# schematic.net
KiCad netlist of a schematic drawn in EAGLE
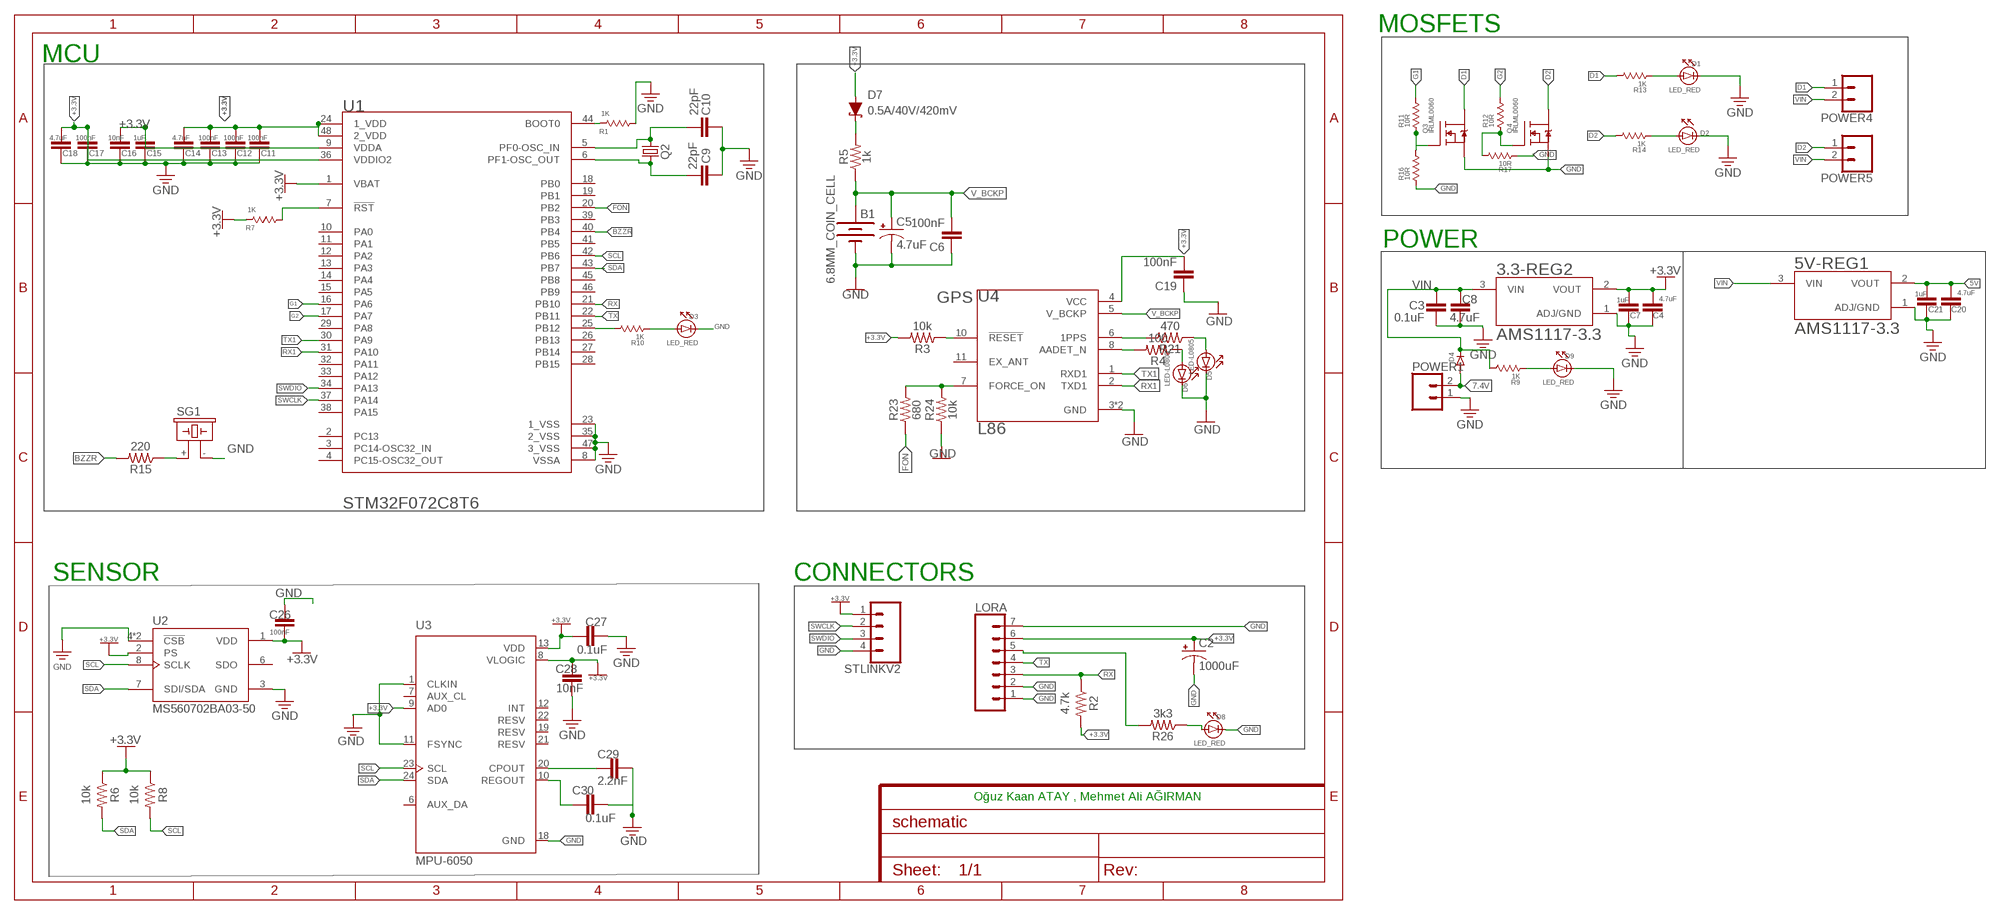
[diagram p0: schematic, sheet 1]

(export (version "E")
  (design (tool "Eeschema 10.0.6"))
  (components
    (comp (ref "3.3-REG2")
      (value "AMS1117-3.3")
      (footprint "eagle-import:SOT229P700X180-4N")
      (fields (field (name "MF") "AMD"))
      (libsource (lib "eagle-import") (part "AMS1117-3.3"))
    )
    (comp (ref "5V-REG1")
      (value "AMS1117-3.3")
      (footprint "eagle-import:SOT229P700X180-4N")
      (fields (field (name "MF") "AMD"))
      (libsource (lib "eagle-import") (part "AMS1117-3.3"))
    )
    (comp (ref "B1")
      (value "6.8MM_COIN_CELL")
      (footprint "eagle-import:BATTCON-6.8MM")
      (libsource (lib "eagle-import") (part "BATTERY-6.8MM_SMD"))
    )
    (comp (ref "C2")
      (value "1000uF")
      (footprint "eagle-import:150CLZ-1010")
      (libsource (lib "eagle-import") (part "CPOL-US150CLZ-1010"))
    )
    (comp (ref "C3")
      (value "0.1uF")
      (footprint "eagle-import:CAPC1608X85")
      (libsource (lib "eagle-import") (part "CCHIP-0603(1608-METRIC)_"))
    )
    (comp (ref "C4")
      (value "4.7uF")
      (footprint "eagle-import:CAPC1608X85")
      (libsource (lib "eagle-import") (part "CCHIP-0603(1608-METRIC)_"))
    )
    (comp (ref "C5")
      (value "4.7uF")
      (footprint "eagle-import:EIA3216")
      (libsource (lib "eagle-import") (part "10UF-POLAR-EIA3216-16V-10%(TANT)"))
    )
    (comp (ref "C6")
      (value "100nF")
      (footprint "eagle-import:0603")
      (libsource (lib "eagle-import") (part "1.0UF-0603-16V-10%"))
    )
    (comp (ref "C7")
      (value "1uF")
      (footprint "eagle-import:CAPC1608X85")
      (libsource (lib "eagle-import") (part "CCHIP-0603(1608-METRIC)_"))
    )
    (comp (ref "C8")
      (value "4.7uF")
      (footprint "eagle-import:CAPC1608X85")
      (libsource (lib "eagle-import") (part "CCHIP-0603(1608-METRIC)_"))
    )
    (comp (ref "C9")
      (value "22pF")
      (footprint "eagle-import:CAPC1608X85")
      (libsource (lib "eagle-import") (part "CCHIP-0603(1608-METRIC)_"))
    )
    (comp (ref "C10")
      (value "22pF")
      (footprint "eagle-import:CAPC1608X85")
      (libsource (lib "eagle-import") (part "CCHIP-0603(1608-METRIC)_"))
    )
    (comp (ref "C11")
      (value "100nF")
      (footprint "eagle-import:CAPC1608X85")
      (libsource (lib "eagle-import") (part "CCHIP-0603(1608-METRIC)_"))
    )
    (comp (ref "C12")
      (value "100nF")
      (footprint "eagle-import:CAPC1608X85")
      (libsource (lib "eagle-import") (part "CCHIP-0603(1608-METRIC)_"))
    )
    (comp (ref "C13")
      (value "100nF")
      (footprint "eagle-import:CAPC1608X85")
      (libsource (lib "eagle-import") (part "CCHIP-0603(1608-METRIC)_"))
    )
    (comp (ref "C14")
      (value "4.7uF")
      (footprint "eagle-import:CAPC1608X85")
      (libsource (lib "eagle-import") (part "CCHIP-0603(1608-METRIC)_"))
    )
    (comp (ref "C15")
      (value "1uF")
      (footprint "eagle-import:CAPC1608X85")
      (libsource (lib "eagle-import") (part "CCHIP-0603(1608-METRIC)_"))
    )
    (comp (ref "C16")
      (value "10nF")
      (footprint "eagle-import:CAPC1608X85")
      (libsource (lib "eagle-import") (part "CCHIP-0603(1608-METRIC)_"))
    )
    (comp (ref "C17")
      (value "100nF")
      (footprint "eagle-import:CAPC1608X85")
      (libsource (lib "eagle-import") (part "CCHIP-0603(1608-METRIC)_"))
    )
    (comp (ref "C18")
      (value "4.7uF")
      (footprint "eagle-import:CAPC1608X85")
      (libsource (lib "eagle-import") (part "CCHIP-0603(1608-METRIC)_"))
    )
    (comp (ref "C19")
      (value "100nF")
      (footprint "eagle-import:0603")
      (libsource (lib "eagle-import") (part "1.0UF-0603-16V-10%"))
    )
    (comp (ref "C20")
      (value "4.7uF")
      (footprint "eagle-import:CAPC1608X85")
      (libsource (lib "eagle-import") (part "CCHIP-0603(1608-METRIC)_"))
    )
    (comp (ref "C21")
      (value "1uF")
      (footprint "eagle-import:CAPC1608X85")
      (libsource (lib "eagle-import") (part "CCHIP-0603(1608-METRIC)_"))
    )
    (comp (ref "C26")
      (value "100nF")
      (footprint "eagle-import:CAPC1608X85")
      (libsource (lib "eagle-import") (part "CCHIP-0603(1608-METRIC)_"))
    )
    (comp (ref "C27")
      (value "0.1uF")
      (footprint "eagle-import:CAPC1608X85")
      (libsource (lib "eagle-import") (part "CCHIP-0603(1608-METRIC)_"))
    )
    (comp (ref "C28")
      (value "10nF")
      (footprint "eagle-import:CAPC1608X85")
      (libsource (lib "eagle-import") (part "CCHIP-0603(1608-METRIC)_"))
    )
    (comp (ref "C29")
      (value "2.2nF")
      (footprint "eagle-import:CAPC1608X85")
      (libsource (lib "eagle-import") (part "CCHIP-0603(1608-METRIC)_"))
    )
    (comp (ref "C30")
      (value "0.1uF")
      (footprint "eagle-import:CAPC1608X85")
      (libsource (lib "eagle-import") (part "CCHIP-0603(1608-METRIC)_"))
    )
    (comp (ref "D1")
      (value "LED_RED")
      (footprint "eagle-import:LED_0805")
      (libsource (lib "eagle-import") (part "LED-L0805"))
    )
    (comp (ref "D2")
      (value "LED_RED")
      (footprint "eagle-import:LED_0805")
      (libsource (lib "eagle-import") (part "LED-L0805"))
    )
    (comp (ref "D3")
      (value "LED_RED")
      (footprint "eagle-import:LED_0805")
      (libsource (lib "eagle-import") (part "LED-L0805"))
    )
    (comp (ref "D4")
      (value "DIODE-SS14-DO214AC")
      (footprint "eagle-import:DO-214AC")
      (libsource (lib "eagle-import") (part "DIODE-SS14-DO214AC"))
    )
    (comp (ref "D5")
      (value "LED-L0805")
      (footprint "eagle-import:LED_0805")
      (libsource (lib "eagle-import") (part "LED-L0805"))
    )
    (comp (ref "D6")
      (value "LED-L0805")
      (footprint "eagle-import:LED_0805")
      (libsource (lib "eagle-import") (part "LED-L0805"))
    )
    (comp (ref "D7")
      (value "0.5A/40V/420mV")
      (footprint "eagle-import:SOD-323")
      (libsource (lib "eagle-import") (part "DIODE-SCHOTTKY-PMEG4005EJ"))
    )
    (comp (ref "D8")
      (value "LED_RED")
      (footprint "eagle-import:LED_0805")
      (libsource (lib "eagle-import") (part "LED-L0805"))
    )
    (comp (ref "D9")
      (value "LED_RED")
      (footprint "eagle-import:LED_0805")
      (libsource (lib "eagle-import") (part "LED-L0805"))
    )
    (comp (ref "LORA")
      (value "CONN_07")
      (footprint "eagle-import:1X07")
      (libsource (lib "eagle-import") (part "CONN_07"))
    )
    (comp (ref "POWER1")
      (value "CONN_023.5MM-NO_SILK")
      (footprint "eagle-import:SCREWTERMINAL-3.5MM-2-NS")
      (libsource (lib "eagle-import") (part "CONN_023.5MM-NO_SILK"))
    )
    (comp (ref "POWER4")
      (value "CONN_023.5MM-NO_SILK")
      (footprint "eagle-import:SCREWTERMINAL-3.5MM-2-NS")
      (libsource (lib "eagle-import") (part "CONN_023.5MM-NO_SILK"))
    )
    (comp (ref "POWER5")
      (value "CONN_023.5MM-NO_SILK")
      (footprint "eagle-import:SCREWTERMINAL-3.5MM-2-NS")
      (libsource (lib "eagle-import") (part "CONN_023.5MM-NO_SILK"))
    )
    (comp (ref "Q2")
      (value "CRYSTALHC49U70")
      (footprint "eagle-import:HC49U70")
      (libsource (lib "eagle-import") (part "CRYSTALHC49U70"))
    )
    (comp (ref "Q3")
      (value "IRLML0060")
      (footprint "eagle-import:SOT-23")
      (libsource (lib "eagle-import") (part "N_CH_MOSFET-SOT23"))
    )
    (comp (ref "Q4")
      (value "IRLML0060")
      (footprint "eagle-import:SOT-23")
      (libsource (lib "eagle-import") (part "N_CH_MOSFET-SOT23"))
    )
    (comp (ref "R1")
      (value "1K")
      (footprint "eagle-import:RES_0805")
      (libsource (lib "eagle-import") (part "RES-R0805"))
    )
    (comp (ref "R2")
      (value "4.7k")
      (footprint "eagle-import:RESC2012X65")
      (libsource (lib "eagle-import") (part "R-USCHIP-0805(2012-METRIC)_"))
    )
    (comp (ref "R3")
      (value "10k")
      (footprint "eagle-import:0603")
      (libsource (lib "eagle-import") (part "SparkFun-Resistors_532_1KOHM-0603-1/10W-1%"))
    )
    (comp (ref "R4")
      (value "100")
      (footprint "eagle-import:0603")
      (libsource (lib "eagle-import") (part "SparkFun-Resistors_532_1KOHM-0603-1/10W-1%"))
    )
    (comp (ref "R5")
      (value "1k")
      (footprint "eagle-import:0603")
      (libsource (lib "eagle-import") (part "1KOHM-0603-1/10W-1%"))
    )
    (comp (ref "R6")
      (value "10k")
      (footprint "eagle-import:RESC2012X65")
      (libsource (lib "eagle-import") (part "R-USCHIP-0805(2012-METRIC)_"))
    )
    (comp (ref "R7")
      (value "1K")
      (footprint "eagle-import:RES_0805")
      (libsource (lib "eagle-import") (part "RES-R0805"))
    )
    (comp (ref "R8")
      (value "10k")
      (footprint "eagle-import:RESC2012X65")
      (libsource (lib "eagle-import") (part "R-USCHIP-0805(2012-METRIC)_"))
    )
    (comp (ref "R9")
      (value "1K")
      (footprint "eagle-import:RES_0805")
      (libsource (lib "eagle-import") (part "RES-R0805"))
    )
    (comp (ref "R10")
      (value "1K")
      (footprint "eagle-import:RES_0805")
      (libsource (lib "eagle-import") (part "RES-R0805"))
    )
    (comp (ref "R11")
      (value "10R")
      (footprint "eagle-import:RES_0805")
      (libsource (lib "eagle-import") (part "RES-R0805"))
    )
    (comp (ref "R12")
      (value "10R")
      (footprint "eagle-import:RES_0805")
      (libsource (lib "eagle-import") (part "RES-R0805"))
    )
    (comp (ref "R13")
      (value "1K")
      (footprint "eagle-import:RES_0805")
      (libsource (lib "eagle-import") (part "RES-R0805"))
    )
    (comp (ref "R14")
      (value "1K")
      (footprint "eagle-import:RES_0805")
      (libsource (lib "eagle-import") (part "RES-R0805"))
    )
    (comp (ref "R15")
      (value "220")
      (footprint "eagle-import:0603")
      (libsource (lib "eagle-import") (part "SparkFun-Resistors_532_1KOHM-0603-1/10W-1%"))
    )
    (comp (ref "R16")
      (value "10R")
      (footprint "eagle-import:RES_0805")
      (libsource (lib "eagle-import") (part "RES-R0805"))
    )
    (comp (ref "R17")
      (value "10R")
      (footprint "eagle-import:RES_0805")
      (libsource (lib "eagle-import") (part "RES-R0805"))
    )
    (comp (ref "R21")
      (value "470")
      (footprint "eagle-import:0603")
      (libsource (lib "eagle-import") (part "SparkFun-Resistors_532_1KOHM-0603-1/10W-1%"))
    )
    (comp (ref "R23")
      (value "680")
      (footprint "eagle-import:0603")
      (libsource (lib "eagle-import") (part "SparkFun-Resistors_532_1KOHM-0603-1/10W-1%"))
    )
    (comp (ref "R24")
      (value "10k")
      (footprint "eagle-import:0603")
      (libsource (lib "eagle-import") (part "SparkFun-Resistors_532_1KOHM-0603-1/10W-1%"))
    )
    (comp (ref "R26")
      (value "3k3")
      (footprint "eagle-import:0603")
      (libsource (lib "eagle-import") (part "SparkFun-Resistors_532_1KOHM-0603-1/10W-1%"))
    )
    (comp (ref "SG1")
      (value "F/CM12P")
      (footprint "eagle-import:F_CM12P")
      (libsource (lib "eagle-import") (part "F/CM12P"))
    )
    (comp (ref "STLINKV2")
      (value "CONN_04")
      (footprint "eagle-import:1X04")
      (libsource (lib "eagle-import") (part "CONN_04"))
    )
    (comp (ref "U1")
      (value "STMICROELECTRONICS_STM32F072C8T6STMICROELECTRONICS_STM32F072C8T6_0_0")
      (footprint "eagle-import:STMICROELECTRONICS_STM32F072C8T6_0")
      (fields
        (field (name "DIGIKEY_PART_NUMBER") "STM32F072C8T6-ND")
        (field (name "MF") "STMicroelectronics")
        (field (name "MOUSER_PART_NUMBER") "511-STM32F072C8T6")
      )
      (libsource (lib "eagle-import") (part "STMICROELECTRONICS_STM32F072C8T6STMICROELECTRONICS_STM32F072C8T6_0_0"))
    )
    (comp (ref "U2")
      (value "MS560702BA03-50")
      (footprint "eagle-import:SON125P300X500X100-8N")
      (fields (field (name "MF") "TE Connectivity"))
      (libsource (lib "eagle-import") (part "MS560702BA03-50"))
    )
    (comp (ref "U3")
      (value "MPU-6050")
      (footprint "eagle-import:QFN50P400X400X95-24N")
      (fields (field (name "MF") "TDK InvenSense"))
      (libsource (lib "eagle-import") (part "MPU-6050"))
    )
    (comp (ref "U4")
      (value "L86")
      (footprint "eagle-import:XCVR_L86")
      (fields (field (name "MF") "Quectel"))
      (libsource (lib "eagle-import") (part "L86"))
    )
  )
  (nets
    (net (code "1") (name "+3.3V") (class "Default")
      (node (ref "3.3-REG2") (pin "2") (pinfunction "VOUT_2") (pintype "output"))
      (node (ref "C11") (pin "1") (pinfunction "1_1") (pintype "passive"))
      (node (ref "C12") (pin "1") (pinfunction "1_1") (pintype "passive"))
      (node (ref "C13") (pin "1") (pinfunction "1_1") (pintype "passive"))
      (node (ref "C14") (pin "1") (pinfunction "1_1") (pintype "passive"))
      (node (ref "C15") (pin "1") (pinfunction "1_1") (pintype "passive"))
      (node (ref "C16") (pin "1") (pinfunction "1_1") (pintype "passive"))
      (node (ref "C17") (pin "1") (pinfunction "1_1") (pintype "passive"))
      (node (ref "C18") (pin "1") (pinfunction "1_1") (pintype "passive"))
      (node (ref "C19") (pin "2") (pinfunction "2_2") (pintype "passive"))
      (node (ref "C2") (pin "+") (pinfunction "+_+") (pintype "passive"))
      (node (ref "C26") (pin "1") (pinfunction "1_1") (pintype "passive"))
      (node (ref "C27") (pin "2") (pinfunction "2_2") (pintype "passive"))
      (node (ref "C28") (pin "2") (pinfunction "2_2") (pintype "passive"))
      (node (ref "C4") (pin "1") (pinfunction "1_1") (pintype "passive"))
      (node (ref "C7") (pin "1") (pinfunction "1_1") (pintype "passive"))
      (node (ref "D7") (pin "A") (pinfunction "A_A") (pintype "passive"))
      (node (ref "LORA") (pin "6") (pinfunction "6_6") (pintype "passive"))
      (node (ref "R2") (pin "2") (pinfunction "2_2") (pintype "passive"))
      (node (ref "R3") (pin "2") (pinfunction "2_2") (pintype "passive"))
      (node (ref "R6") (pin "1") (pinfunction "1_1") (pintype "passive"))
      (node (ref "R7") (pin "B") (pinfunction "B_B") (pintype "bidirectional"))
      (node (ref "R8") (pin "1") (pinfunction "1_1") (pintype "passive"))
      (node (ref "STLINKV2") (pin "1") (pinfunction "1_1") (pintype "passive"))
      (node (ref "U1") (pin "1") (pinfunction "VBAT_1") (pintype "bidirectional"))
      (node (ref "U1") (pin "24") (pinfunction "1_VDD_24") (pintype "bidirectional"))
      (node (ref "U1") (pin "36") (pinfunction "VDDIO2_36") (pintype "bidirectional"))
      (node (ref "U1") (pin "48") (pinfunction "2_VDD_48") (pintype "bidirectional"))
      (node (ref "U1") (pin "9") (pinfunction "VDDA_9") (pintype "bidirectional"))
      (node (ref "U2") (pin "1") (pinfunction "VDD_1") (pintype "power_in"))
      (node (ref "U2") (pin "2") (pinfunction "PS_2") (pintype "input"))
      (node (ref "U3") (pin "13") (pinfunction "VDD_13") (pintype "power_in"))
      (node (ref "U3") (pin "8") (pinfunction "VLOGIC_8") (pintype "power_in"))
      (node (ref "U3") (pin "9") (pinfunction "AD0_9") (pintype "input"))
      (node (ref "U4") (pin "4") (pinfunction "VCC_4") (pintype "power_in"))
    )
    (net (code "2") (name "5V") (class "Default")
      (node (ref "5V-REG1") (pin "2") (pinfunction "VOUT_2") (pintype "output"))
      (node (ref "C20") (pin "1") (pinfunction "1_1") (pintype "passive"))
      (node (ref "C21") (pin "1") (pinfunction "1_1") (pintype "passive"))
    )
    (net (code "3") (name "7.4V") (class "Default")
      (node (ref "D4") (pin "A") (pinfunction "ANOT_A") (pintype "bidirectional"))
      (node (ref "POWER1") (pin "2") (pinfunction "2_2") (pintype "passive"))
    )
    (net (code "4") (name "BZZR") (class "Default")
      (node (ref "R15") (pin "2") (pinfunction "2_2") (pintype "passive"))
      (node (ref "U1") (pin "40") (pinfunction "PB4_40") (pintype "bidirectional"))
    )
    (net (code "5") (name "D1") (class "Default")
      (node (ref "POWER4") (pin "1") (pinfunction "1_1") (pintype "passive"))
      (node (ref "Q3") (pin "3") (pinfunction "D_3") (pintype "bidirectional"))
      (node (ref "R13") (pin "B") (pinfunction "B_B") (pintype "bidirectional"))
    )
    (net (code "6") (name "D2") (class "Default")
      (node (ref "POWER5") (pin "1") (pinfunction "1_1") (pintype "passive"))
      (node (ref "Q4") (pin "3") (pinfunction "D_3") (pintype "bidirectional"))
      (node (ref "R14") (pin "B") (pinfunction "B_B") (pintype "bidirectional"))
    )
    (net (code "7") (name "FON") (class "Default")
      (node (ref "R23") (pin "1") (pinfunction "1_1") (pintype "passive"))
      (node (ref "U1") (pin "20") (pinfunction "PB2_20") (pintype "bidirectional"))
    )
    (net (code "8") (name "G1") (class "Default")
      (node (ref "R11") (pin "B") (pinfunction "B_B") (pintype "bidirectional"))
      (node (ref "U1") (pin "16") (pinfunction "PA6_16") (pintype "bidirectional"))
    )
    (net (code "9") (name "G2") (class "Default")
      (node (ref "R12") (pin "B") (pinfunction "B_B") (pintype "bidirectional"))
      (node (ref "U1") (pin "17") (pinfunction "PA7_17") (pintype "bidirectional"))
    )
    (net (code "10") (name "GND") (class "Default")
      (node (ref "3.3-REG2") (pin "1") (pinfunction "ADJ/GND_1") (pintype "power_in"))
      (node (ref "5V-REG1") (pin "1") (pinfunction "ADJ/GND_1") (pintype "power_in"))
      (node (ref "B1") (pin "-") (pinfunction "-_-") (pintype "power_in"))
      (node (ref "C10") (pin "2") (pinfunction "2_2") (pintype "passive"))
      (node (ref "C11") (pin "2") (pinfunction "2_2") (pintype "passive"))
      (node (ref "C12") (pin "2") (pinfunction "2_2") (pintype "passive"))
      (node (ref "C13") (pin "2") (pinfunction "2_2") (pintype "passive"))
      (node (ref "C14") (pin "2") (pinfunction "2_2") (pintype "passive"))
      (node (ref "C15") (pin "2") (pinfunction "2_2") (pintype "passive"))
      (node (ref "C16") (pin "2") (pinfunction "2_2") (pintype "passive"))
      (node (ref "C17") (pin "2") (pinfunction "2_2") (pintype "passive"))
      (node (ref "C18") (pin "2") (pinfunction "2_2") (pintype "passive"))
      (node (ref "C19") (pin "1") (pinfunction "1_1") (pintype "passive"))
      (node (ref "C2") (pin "-") (pinfunction "-_-") (pintype "passive"))
      (node (ref "C20") (pin "2") (pinfunction "2_2") (pintype "passive"))
      (node (ref "C21") (pin "2") (pinfunction "2_2") (pintype "passive"))
      (node (ref "C26") (pin "2") (pinfunction "2_2") (pintype "passive"))
      (node (ref "C27") (pin "1") (pinfunction "1_1") (pintype "passive"))
      (node (ref "C28") (pin "1") (pinfunction "1_1") (pintype "passive"))
      (node (ref "C29") (pin "1") (pinfunction "1_1") (pintype "passive"))
      (node (ref "C3") (pin "1") (pinfunction "1_1") (pintype "passive"))
      (node (ref "C30") (pin "1") (pinfunction "1_1") (pintype "passive"))
      (node (ref "C4") (pin "2") (pinfunction "2_2") (pintype "passive"))
      (node (ref "C5") (pin "-") (pinfunction "-_-") (pintype "passive"))
      (node (ref "C6") (pin "1") (pinfunction "1_1") (pintype "passive"))
      (node (ref "C7") (pin "2") (pinfunction "2_2") (pintype "passive"))
      (node (ref "C8") (pin "1") (pinfunction "1_1") (pintype "passive"))
      (node (ref "C9") (pin "2") (pinfunction "2_2") (pintype "passive"))
      (node (ref "D1") (pin "K") (pinfunction "KATOT_K") (pintype "bidirectional"))
      (node (ref "D2") (pin "K") (pinfunction "KATOT_K") (pintype "bidirectional"))
      (node (ref "D3") (pin "K") (pinfunction "KATOT_K") (pintype "bidirectional"))
      (node (ref "D5") (pin "K") (pinfunction "KATOT_K") (pintype "bidirectional"))
      (node (ref "D6") (pin "K") (pinfunction "KATOT_K") (pintype "bidirectional"))
      (node (ref "D8") (pin "K") (pinfunction "KATOT_K") (pintype "bidirectional"))
      (node (ref "D9") (pin "K") (pinfunction "KATOT_K") (pintype "bidirectional"))
      (node (ref "LORA") (pin "1") (pinfunction "1_1") (pintype "passive"))
      (node (ref "LORA") (pin "2") (pinfunction "2_2") (pintype "passive"))
      (node (ref "LORA") (pin "7") (pinfunction "7_7") (pintype "passive"))
      (node (ref "POWER1") (pin "1") (pinfunction "1_1") (pintype "passive"))
      (node (ref "Q3") (pin "2") (pinfunction "S_2") (pintype "bidirectional"))
      (node (ref "Q4") (pin "2") (pinfunction "S_2") (pintype "bidirectional"))
      (node (ref "R1") (pin "A") (pinfunction "A_A") (pintype "bidirectional"))
      (node (ref "R16") (pin "A") (pinfunction "A_A") (pintype "bidirectional"))
      (node (ref "R17") (pin "A") (pinfunction "A_A") (pintype "bidirectional"))
      (node (ref "R24") (pin "1") (pinfunction "1_1") (pintype "passive"))
      (node (ref "SG1") (pin "-") (pinfunction "2_-") (pintype "passive"))
      (node (ref "STLINKV2") (pin "4") (pinfunction "4_4") (pintype "passive"))
      (node (ref "U1") (pin "23") (pinfunction "1_VSS_23") (pintype "bidirectional"))
      (node (ref "U1") (pin "35") (pinfunction "2_VSS_35") (pintype "bidirectional"))
      (node (ref "U1") (pin "47") (pinfunction "3_VSS_47") (pintype "bidirectional"))
      (node (ref "U1") (pin "8") (pinfunction "VSSA_8") (pintype "bidirectional"))
      (node (ref "U2") (pin "3") (pinfunction "GND_3") (pintype "power_in"))
      (node (ref "U2") (pin "4") (pinfunction "~{CSB}_4") (pintype "input"))
      (node (ref "U2") (pin "5") (pinfunction "~{CSB}_5") (pintype "input"))
      (node (ref "U3") (pin "1") (pinfunction "CLKIN_1") (pintype "input"))
      (node (ref "U3") (pin "11") (pinfunction "FSYNC_11") (pintype "input"))
      (node (ref "U3") (pin "18") (pinfunction "GND_18") (pintype "power_in"))
      (node (ref "U4") (pin "12") (pinfunction "GND_12") (pintype "passive"))
      (node (ref "U4") (pin "3") (pinfunction "GND_3") (pintype "passive"))
    )
    (net (code "11") (name "Net-(D1-ANOT)") (class "Default")
      (node (ref "D1") (pin "A") (pinfunction "ANOT_A") (pintype "bidirectional"))
      (node (ref "R13") (pin "A") (pinfunction "A_A") (pintype "bidirectional"))
    )
    (net (code "12") (name "Net-(D2-ANOT)") (class "Default")
      (node (ref "D2") (pin "A") (pinfunction "ANOT_A") (pintype "bidirectional"))
      (node (ref "R14") (pin "A") (pinfunction "A_A") (pintype "bidirectional"))
    )
    (net (code "13") (name "Net-(D3-ANOT)") (class "Default")
      (node (ref "D3") (pin "A") (pinfunction "ANOT_A") (pintype "bidirectional"))
      (node (ref "R10") (pin "A") (pinfunction "A_A") (pintype "bidirectional"))
    )
    (net (code "14") (name "Net-(D5-ANOT)") (class "Default")
      (node (ref "D5") (pin "A") (pinfunction "ANOT_A") (pintype "bidirectional"))
      (node (ref "R21") (pin "1") (pinfunction "1_1") (pintype "passive"))
    )
    (net (code "15") (name "Net-(D6-ANOT)") (class "Default")
      (node (ref "D6") (pin "A") (pinfunction "ANOT_A") (pintype "bidirectional"))
      (node (ref "R4") (pin "1") (pinfunction "1_1") (pintype "passive"))
    )
    (net (code "16") (name "Net-(D7-PadC)") (class "Default")
      (node (ref "D7") (pin "C") (pinfunction "C_C") (pintype "passive"))
      (node (ref "R5") (pin "2") (pinfunction "2_2") (pintype "passive"))
    )
    (net (code "17") (name "Net-(D8-ANOT)") (class "Default")
      (node (ref "D8") (pin "A") (pinfunction "ANOT_A") (pintype "bidirectional"))
      (node (ref "R26") (pin "1") (pinfunction "1_1") (pintype "passive"))
    )
    (net (code "18") (name "Net-(D9-ANOT)") (class "Default")
      (node (ref "D9") (pin "A") (pinfunction "ANOT_A") (pintype "bidirectional"))
      (node (ref "R9") (pin "A") (pinfunction "A_A") (pintype "bidirectional"))
    )
    (net (code "19") (name "Net-(LORA-Pad5)") (class "Default")
      (node (ref "LORA") (pin "5") (pinfunction "5_5") (pintype "passive"))
      (node (ref "R26") (pin "2") (pinfunction "2_2") (pintype "passive"))
    )
    (net (code "20") (name "Net-(Q3-G)") (class "Default")
      (node (ref "Q3") (pin "1") (pinfunction "G_1") (pintype "bidirectional"))
      (node (ref "R11") (pin "A") (pinfunction "A_A") (pintype "bidirectional"))
      (node (ref "R16") (pin "B") (pinfunction "B_B") (pintype "bidirectional"))
    )
    (net (code "21") (name "Net-(Q4-G)") (class "Default")
      (node (ref "Q4") (pin "1") (pinfunction "G_1") (pintype "bidirectional"))
      (node (ref "R12") (pin "A") (pinfunction "A_A") (pintype "bidirectional"))
      (node (ref "R17") (pin "B") (pinfunction "B_B") (pintype "bidirectional"))
    )
    (net (code "22") (name "Net-(SG1-1)") (class "Default")
      (node (ref "R15") (pin "1") (pinfunction "1_1") (pintype "passive"))
      (node (ref "SG1") (pin "+") (pinfunction "1_+") (pintype "passive"))
    )
    (net (code "23") (name "Net-(U1-BOOT0)") (class "Default")
      (node (ref "R1") (pin "B") (pinfunction "B_B") (pintype "bidirectional"))
      (node (ref "U1") (pin "44") (pinfunction "BOOT0_44") (pintype "bidirectional"))
    )
    (net (code "24") (name "Net-(U1-PB12)") (class "Default")
      (node (ref "R10") (pin "B") (pinfunction "B_B") (pintype "bidirectional"))
      (node (ref "U1") (pin "25") (pinfunction "PB12_25") (pintype "bidirectional"))
    )
    (net (code "25") (name "Net-(U1-PF0-OSC_IN)") (class "Default")
      (node (ref "C10") (pin "1") (pinfunction "1_1") (pintype "passive"))
      (node (ref "Q2") (pin "1") (pinfunction "1_1") (pintype "passive"))
      (node (ref "U1") (pin "5") (pinfunction "PF0-OSC_IN_5") (pintype "bidirectional"))
    )
    (net (code "26") (name "Net-(U1-PF1-OSC_OUT)") (class "Default")
      (node (ref "C9") (pin "1") (pinfunction "1_1") (pintype "passive"))
      (node (ref "Q2") (pin "2") (pinfunction "2_2") (pintype "passive"))
      (node (ref "U1") (pin "6") (pinfunction "PF1-OSC_OUT_6") (pintype "bidirectional"))
    )
    (net (code "27") (name "Net-(U1-~{RST})") (class "Default")
      (node (ref "R7") (pin "A") (pinfunction "A_A") (pintype "bidirectional"))
      (node (ref "U1") (pin "7") (pinfunction "~{RST}_7") (pintype "bidirectional"))
    )
    (net (code "28") (name "Net-(U3-CPOUT)") (class "Default")
      (node (ref "C29") (pin "2") (pinfunction "2_2") (pintype "passive"))
      (node (ref "U3") (pin "20") (pinfunction "CPOUT_20") (pintype "passive"))
    )
    (net (code "29") (name "Net-(U3-REGOUT)") (class "Default")
      (node (ref "C30") (pin "2") (pinfunction "2_2") (pintype "passive"))
      (node (ref "U3") (pin "10") (pinfunction "REGOUT_10") (pintype "passive"))
    )
    (net (code "30") (name "Net-(U4-1PPS)") (class "Default")
      (node (ref "R21") (pin "2") (pinfunction "2_2") (pintype "passive"))
      (node (ref "U4") (pin "6") (pinfunction "1PPS_6") (pintype "output"))
    )
    (net (code "31") (name "Net-(U4-AADET_N)") (class "Default")
      (node (ref "R4") (pin "2") (pinfunction "2_2") (pintype "passive"))
      (node (ref "U4") (pin "8") (pinfunction "AADET_N_8") (pintype "output"))
    )
    (net (code "32") (name "Net-(U4-FORCE_ON)") (class "Default")
      (node (ref "R23") (pin "2") (pinfunction "2_2") (pintype "passive"))
      (node (ref "R24") (pin "2") (pinfunction "2_2") (pintype "passive"))
      (node (ref "U4") (pin "7") (pinfunction "FORCE_ON_7") (pintype "input"))
    )
    (net (code "33") (name "Net-(U4-~{RESET})") (class "Default")
      (node (ref "R3") (pin "1") (pinfunction "1_1") (pintype "passive"))
      (node (ref "U4") (pin "10") (pinfunction "~{RESET}_10") (pintype "input"))
    )
    (net (code "34") (name "RX") (class "Default")
      (node (ref "LORA") (pin "3") (pinfunction "3_3") (pintype "passive"))
      (node (ref "R2") (pin "1") (pinfunction "1_1") (pintype "passive"))
      (node (ref "U1") (pin "21") (pinfunction "PB10_21") (pintype "bidirectional"))
    )
    (net (code "35") (name "RX1") (class "Default")
      (node (ref "U1") (pin "31") (pinfunction "PA10_31") (pintype "bidirectional"))
      (node (ref "U4") (pin "2") (pinfunction "TXD1_2") (pintype "output"))
    )
    (net (code "36") (name "SCL") (class "Default")
      (node (ref "R8") (pin "2") (pinfunction "2_2") (pintype "passive"))
      (node (ref "U1") (pin "42") (pinfunction "PB6_42") (pintype "bidirectional"))
      (node (ref "U2") (pin "8") (pinfunction "SCLK_8") (pintype "input"))
      (node (ref "U3") (pin "23") (pinfunction "SCL_23") (pintype "input"))
    )
    (net (code "37") (name "SDA") (class "Default")
      (node (ref "R6") (pin "2") (pinfunction "2_2") (pintype "passive"))
      (node (ref "U1") (pin "43") (pinfunction "PB7_43") (pintype "bidirectional"))
      (node (ref "U2") (pin "7") (pinfunction "SDI/SDA_7") (pintype "bidirectional"))
      (node (ref "U3") (pin "24") (pinfunction "SDA_24") (pintype "bidirectional"))
    )
    (net (code "38") (name "SWCLK") (class "Default")
      (node (ref "STLINKV2") (pin "2") (pinfunction "2_2") (pintype "passive"))
      (node (ref "U1") (pin "37") (pinfunction "PA14_37") (pintype "bidirectional"))
    )
    (net (code "39") (name "SWDIO") (class "Default")
      (node (ref "STLINKV2") (pin "3") (pinfunction "3_3") (pintype "passive"))
      (node (ref "U1") (pin "34") (pinfunction "PA13_34") (pintype "bidirectional"))
    )
    (net (code "40") (name "TX") (class "Default")
      (node (ref "LORA") (pin "4") (pinfunction "4_4") (pintype "passive"))
      (node (ref "U1") (pin "22") (pinfunction "PB11_22") (pintype "bidirectional"))
    )
    (net (code "41") (name "TX1") (class "Default")
      (node (ref "U1") (pin "30") (pinfunction "PA9_30") (pintype "bidirectional"))
      (node (ref "U4") (pin "1") (pinfunction "RXD1_1") (pintype "input"))
    )
    (net (code "42") (name "VIN") (class "Default")
      (node (ref "3.3-REG2") (pin "3") (pinfunction "VIN_3") (pintype "input"))
      (node (ref "5V-REG1") (pin "3") (pinfunction "VIN_3") (pintype "input"))
      (node (ref "C3") (pin "2") (pinfunction "2_2") (pintype "passive"))
      (node (ref "C8") (pin "2") (pinfunction "2_2") (pintype "passive"))
      (node (ref "D4") (pin "K") (pinfunction "KATOT_K") (pintype "bidirectional"))
      (node (ref "POWER4") (pin "2") (pinfunction "2_2") (pintype "passive"))
      (node (ref "POWER5") (pin "2") (pinfunction "2_2") (pintype "passive"))
      (node (ref "R9") (pin "B") (pinfunction "B_B") (pintype "bidirectional"))
    )
    (net (code "43") (name "V_BCKP") (class "Default")
      (node (ref "B1") (pin "+") (pinfunction "+_+") (pintype "power_in"))
      (node (ref "C5") (pin "+") (pinfunction "+_+") (pintype "passive"))
      (node (ref "C6") (pin "2") (pinfunction "2_2") (pintype "passive"))
      (node (ref "R5") (pin "1") (pinfunction "1_1") (pintype "passive"))
      (node (ref "U4") (pin "5") (pinfunction "V_BCKP_5") (pintype "power_in"))
    )
    (net (code "44") (name "unconnected-(U1-PA0-Pad10)") (class "Default")
      (node (ref "U1") (pin "10") (pinfunction "PA0_10") (pintype "bidirectional"))
    )
    (net (code "45") (name "unconnected-(U1-PA1-Pad11)") (class "Default")
      (node (ref "U1") (pin "11") (pinfunction "PA1_11") (pintype "bidirectional"))
    )
    (net (code "46") (name "unconnected-(U1-PA2-Pad12)") (class "Default")
      (node (ref "U1") (pin "12") (pinfunction "PA2_12") (pintype "bidirectional"))
    )
    (net (code "47") (name "unconnected-(U1-PA3-Pad13)") (class "Default")
      (node (ref "U1") (pin "13") (pinfunction "PA3_13") (pintype "bidirectional"))
    )
    (net (code "48") (name "unconnected-(U1-PA4-Pad14)") (class "Default")
      (node (ref "U1") (pin "14") (pinfunction "PA4_14") (pintype "bidirectional"))
    )
    (net (code "49") (name "unconnected-(U1-PA5-Pad15)") (class "Default")
      (node (ref "U1") (pin "15") (pinfunction "PA5_15") (pintype "bidirectional"))
    )
    (net (code "50") (name "unconnected-(U1-PA8-Pad29)") (class "Default")
      (node (ref "U1") (pin "29") (pinfunction "PA8_29") (pintype "bidirectional"))
    )
    (net (code "51") (name "unconnected-(U1-PA11-Pad32)") (class "Default")
      (node (ref "U1") (pin "32") (pinfunction "PA11_32") (pintype "bidirectional"))
    )
    (net (code "52") (name "unconnected-(U1-PA12-Pad33)") (class "Default")
      (node (ref "U1") (pin "33") (pinfunction "PA12_33") (pintype "bidirectional"))
    )
    (net (code "53") (name "unconnected-(U1-PA15-Pad38)") (class "Default")
      (node (ref "U1") (pin "38") (pinfunction "PA15_38") (pintype "bidirectional"))
    )
    (net (code "54") (name "unconnected-(U1-PB0-Pad18)") (class "Default")
      (node (ref "U1") (pin "18") (pinfunction "PB0_18") (pintype "bidirectional"))
    )
    (net (code "55") (name "unconnected-(U1-PB1-Pad19)") (class "Default")
      (node (ref "U1") (pin "19") (pinfunction "PB1_19") (pintype "bidirectional"))
    )
    (net (code "56") (name "unconnected-(U1-PB3-Pad39)") (class "Default")
      (node (ref "U1") (pin "39") (pinfunction "PB3_39") (pintype "bidirectional"))
    )
    (net (code "57") (name "unconnected-(U1-PB5-Pad41)") (class "Default")
      (node (ref "U1") (pin "41") (pinfunction "PB5_41") (pintype "bidirectional"))
    )
    (net (code "58") (name "unconnected-(U1-PB8-Pad45)") (class "Default")
      (node (ref "U1") (pin "45") (pinfunction "PB8_45") (pintype "bidirectional"))
    )
    (net (code "59") (name "unconnected-(U1-PB9-Pad46)") (class "Default")
      (node (ref "U1") (pin "46") (pinfunction "PB9_46") (pintype "bidirectional"))
    )
    (net (code "60") (name "unconnected-(U1-PB13-Pad26)") (class "Default")
      (node (ref "U1") (pin "26") (pinfunction "PB13_26") (pintype "bidirectional"))
    )
    (net (code "61") (name "unconnected-(U1-PB14-Pad27)") (class "Default")
      (node (ref "U1") (pin "27") (pinfunction "PB14_27") (pintype "bidirectional"))
    )
    (net (code "62") (name "unconnected-(U1-PB15-Pad28)") (class "Default")
      (node (ref "U1") (pin "28") (pinfunction "PB15_28") (pintype "bidirectional"))
    )
    (net (code "63") (name "unconnected-(U1-PC13-Pad2)") (class "Default")
      (node (ref "U1") (pin "2") (pinfunction "PC13_2") (pintype "bidirectional"))
    )
    (net (code "64") (name "unconnected-(U1-PC14-OSC32_IN-Pad3)") (class "Default")
      (node (ref "U1") (pin "3") (pinfunction "PC14-OSC32_IN_3") (pintype "bidirectional"))
    )
    (net (code "65") (name "unconnected-(U1-PC15-OSC32_OUT-Pad4)") (class "Default")
      (node (ref "U1") (pin "4") (pinfunction "PC15-OSC32_OUT_4") (pintype "bidirectional"))
    )
    (net (code "66") (name "unconnected-(U2-SDO-Pad6)") (class "Default")
      (node (ref "U2") (pin "6") (pinfunction "SDO_6") (pintype "output"))
    )
    (net (code "67") (name "unconnected-(U3-AUX_CL-Pad7)") (class "Default")
      (node (ref "U3") (pin "7") (pinfunction "AUX_CL_7") (pintype "input"))
    )
    (net (code "68") (name "unconnected-(U3-AUX_DA-Pad6)") (class "Default")
      (node (ref "U3") (pin "6") (pinfunction "AUX_DA_6") (pintype "bidirectional"))
    )
    (net (code "69") (name "unconnected-(U3-INT-Pad12)") (class "Default")
      (node (ref "U3") (pin "12") (pinfunction "INT_12") (pintype "output"))
    )
    (net (code "70") (name "unconnected-(U3-RESV-Pad19)") (class "Default")
      (node (ref "U3") (pin "19") (pinfunction "RESV_19") (pintype "passive"))
    )
    (net (code "71") (name "unconnected-(U3-RESV-Pad21)") (class "Default")
      (node (ref "U3") (pin "21") (pinfunction "RESV_21") (pintype "passive"))
    )
    (net (code "72") (name "unconnected-(U3-RESV-Pad22)") (class "Default")
      (node (ref "U3") (pin "22") (pinfunction "RESV_22") (pintype "passive"))
    )
    (net (code "73") (name "unconnected-(U4-EX_ANT-Pad11)") (class "Default")
      (node (ref "U4") (pin "11") (pinfunction "EX_ANT_11") (pintype "input"))
    )
  )
)
